# 05_USB_HUB.net
KiCad netlist of a schematic drawn in Altium Designer
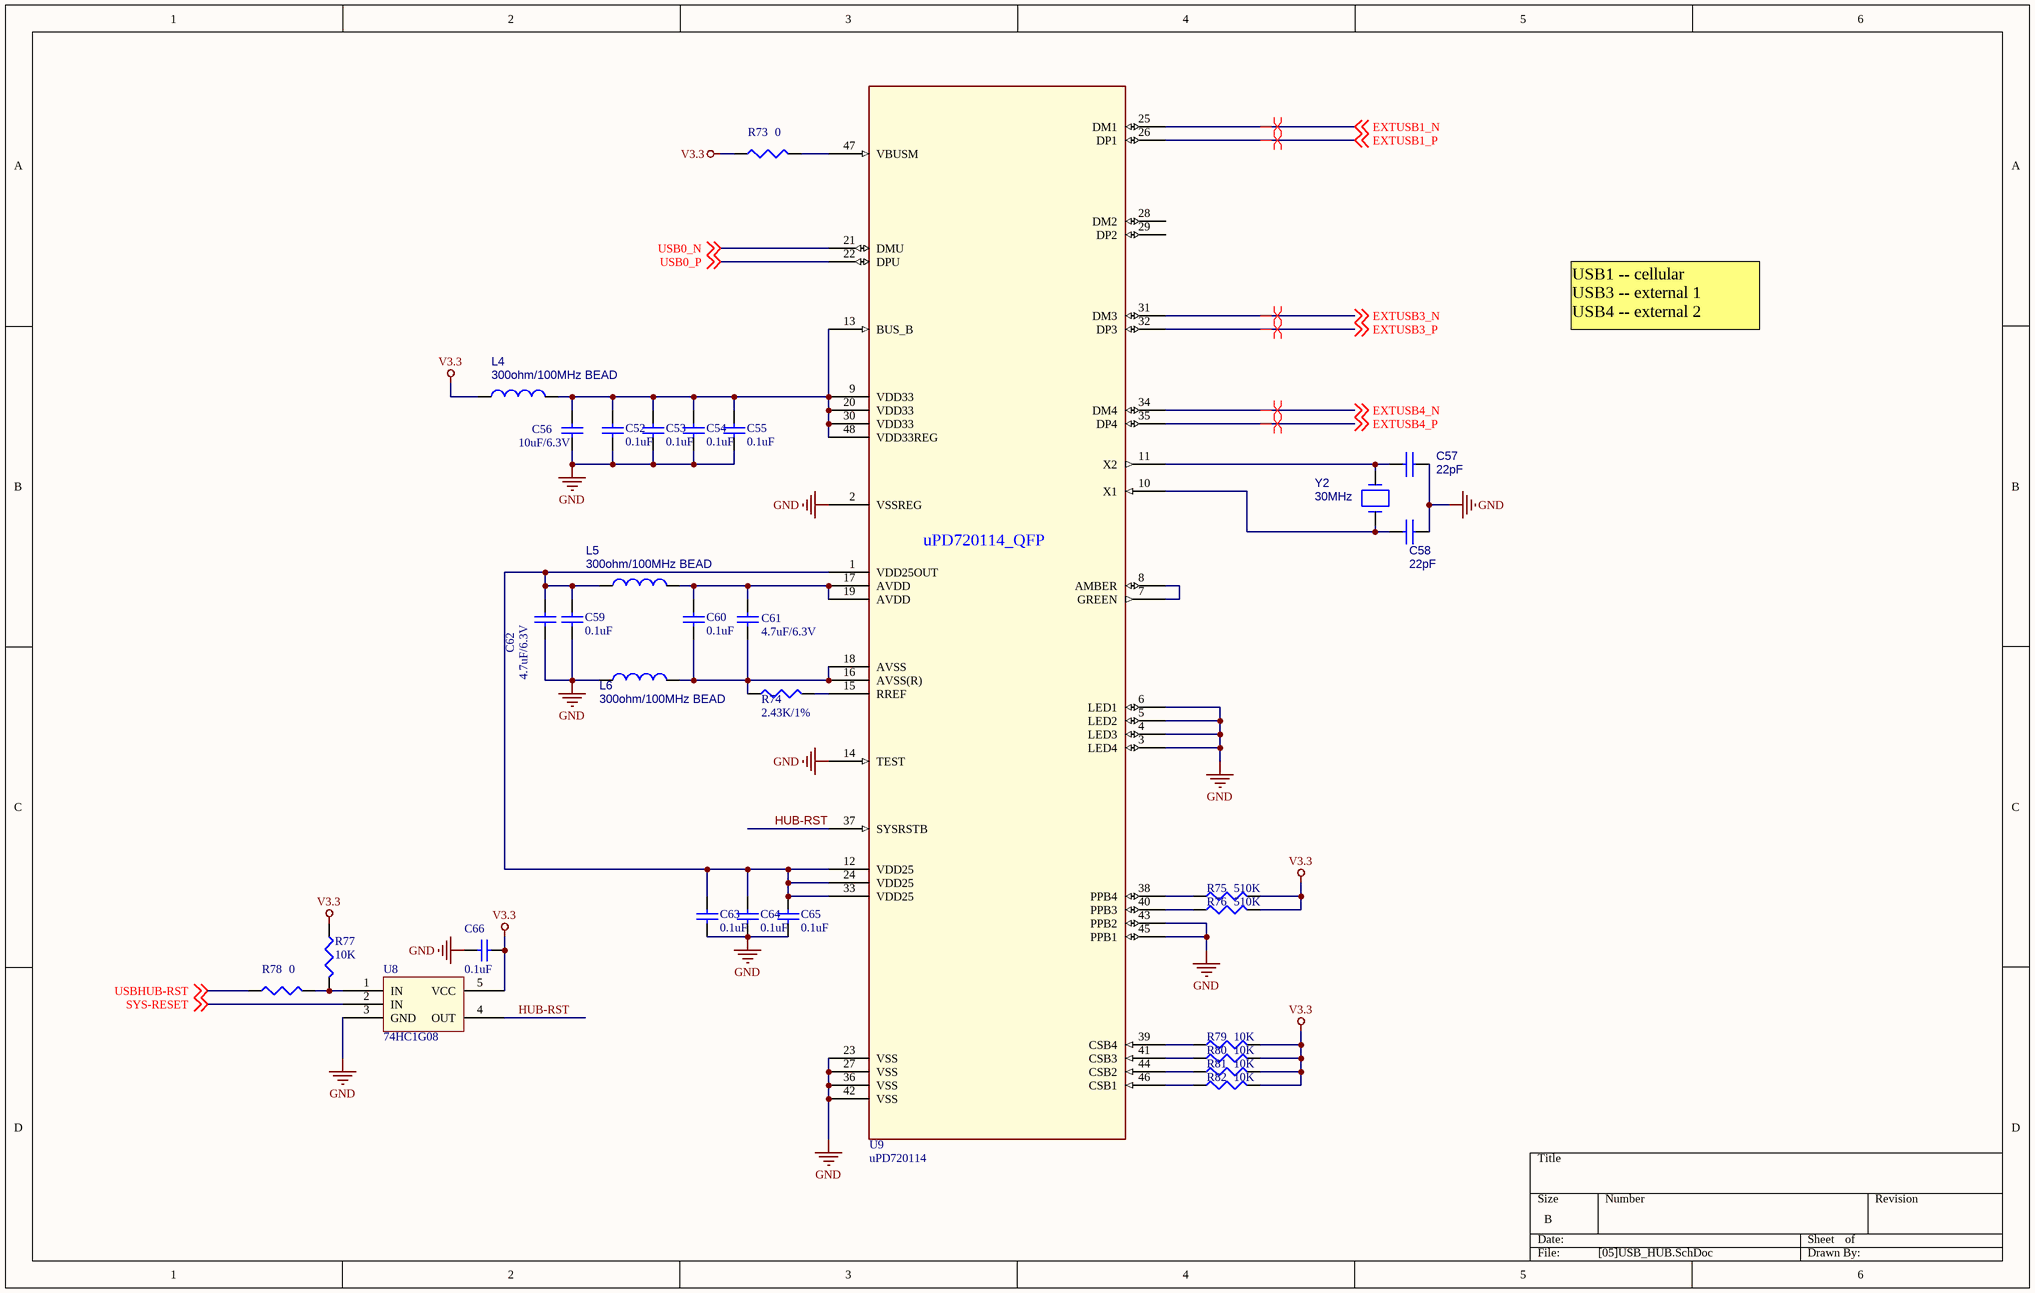
[diagram p0: [05]USB_HUB.SchDoc]

(export (version "E")
  (design (tool "Eeschema 10.0.6"))
  (components
    (comp (ref "C52")
      (value "0.1uF")
      (footprint "0603")
      (description "Capacitor")
      (libsource (lib "Miscellaneous Devices") (part "Cap"))
    )
    (comp (ref "C53")
      (value "0.1uF")
      (footprint "0603")
      (description "Capacitor")
      (libsource (lib "Miscellaneous Devices") (part "Cap"))
    )
    (comp (ref "C54")
      (value "0.1uF")
      (footprint "0603")
      (description "Capacitor")
      (libsource (lib "Miscellaneous Devices") (part "Cap"))
    )
    (comp (ref "C55")
      (value "0.1uF")
      (footprint "0603")
      (description "Capacitor")
      (libsource (lib "Miscellaneous Devices") (part "Cap"))
    )
    (comp (ref "C56")
      (value "10uF/6.3V")
      (footprint "0805")
      (description "Capacitor")
      (libsource (lib "Miscellaneous Devices") (part "Cap"))
    )
    (comp (ref "C57") (value "22pF") (libsource (lib "*") (part "CAP_Dup1")))
    (comp (ref "C58") (value "22pF") (libsource (lib "*") (part "CAP_Dup1")))
    (comp (ref "C59")
      (value "0.1uF")
      (footprint "0603")
      (description "Capacitor")
      (libsource (lib "Miscellaneous Devices") (part "Cap"))
    )
    (comp (ref "C60")
      (value "0.1uF")
      (footprint "0603")
      (description "Capacitor")
      (libsource (lib "Miscellaneous Devices") (part "Cap"))
    )
    (comp (ref "C61")
      (value "4.7uF/6.3V")
      (footprint "0603")
      (description "Capacitor")
      (libsource (lib "Miscellaneous Devices") (part "Cap"))
    )
    (comp (ref "C62")
      (value "4.7uF/6.3V")
      (footprint "0603")
      (description "Capacitor")
      (libsource (lib "Miscellaneous Devices") (part "Cap"))
    )
    (comp (ref "C63")
      (value "0.1uF")
      (footprint "0603")
      (description "Capacitor")
      (libsource (lib "Miscellaneous Devices") (part "Cap"))
    )
    (comp (ref "C64")
      (value "0.1uF")
      (footprint "0603")
      (description "Capacitor")
      (libsource (lib "Miscellaneous Devices") (part "Cap"))
    )
    (comp (ref "C65")
      (value "0.1uF")
      (footprint "0603")
      (description "Capacitor")
      (libsource (lib "Miscellaneous Devices") (part "Cap"))
    )
    (comp (ref "C66")
      (value "0.1uF")
      (footprint "0603")
      (description "Capacitor")
      (libsource (lib "Miscellaneous Devices") (part "Cap"))
    )
    (comp (ref "L4") (value "300ohm/100MHz BEAD") (libsource (lib "*") (part "INDUCTOR_4")))
    (comp (ref "L5") (value "300ohm/100MHz BEAD") (libsource (lib "*") (part "INDUCTOR_4")))
    (comp (ref "L6") (value "300ohm/100MHz BEAD") (libsource (lib "*") (part "INDUCTOR_4")))
    (comp (ref "R73")
      (value "0")
      (footprint "0603")
      (description "Resistor")
      (libsource (lib "Miscellaneous Devices") (part "Res3"))
    )
    (comp (ref "R74")
      (value "2.43K/1%")
      (footprint "0603")
      (description "Resistor")
      (libsource (lib "Miscellaneous Devices") (part "Res3"))
    )
    (comp (ref "R75")
      (value "510K")
      (footprint "0603")
      (description "Resistor")
      (libsource (lib "Miscellaneous Devices") (part "Res3"))
    )
    (comp (ref "R76")
      (value "510K")
      (footprint "0603")
      (description "Resistor")
      (libsource (lib "Miscellaneous Devices") (part "Res3"))
    )
    (comp (ref "R77")
      (value "10K")
      (footprint "0603")
      (description "Resistor")
      (libsource (lib "Miscellaneous Devices") (part "Res3"))
    )
    (comp (ref "R78")
      (value "0")
      (footprint "0603")
      (description "Resistor")
      (libsource (lib "Miscellaneous Devices") (part "Res3"))
    )
    (comp (ref "R79")
      (value "10K")
      (footprint "0603")
      (description "Resistor")
      (libsource (lib "Miscellaneous Devices") (part "Res3"))
    )
    (comp (ref "R80")
      (value "10K")
      (footprint "0603")
      (description "Resistor")
      (libsource (lib "Miscellaneous Devices") (part "Res3"))
    )
    (comp (ref "R81")
      (value "10K")
      (footprint "0603")
      (description "Resistor")
      (libsource (lib "Miscellaneous Devices") (part "Res3"))
    )
    (comp (ref "R82")
      (value "10K")
      (footprint "0603")
      (description "Resistor")
      (libsource (lib "Miscellaneous Devices") (part "Res3"))
    )
    (comp (ref "U8") (value "74HC1G08") (footprint "SOT23-5") (libsource (lib "Schlib") (part "74HC1G08")))
    (comp (ref "U9") (value "uPD720114") (footprint "LQFP48") (libsource (lib "*") (part "upd720114_QFP_4")))
    (comp (ref "Y2") (value "30MHz") (libsource (lib "*") (part "CRYSTAL")))
  )
  (nets
    (net (code "1") (name "/HUB-RST") (class "Default")
      (node (ref "U8") (pin "4") (pinfunction "OUT_4") (pintype "passive"))
      (node (ref "U9") (pin "37") (pinfunction "SYSRSTB_37") (pintype "input"))
    )
    (net (code "2") (name "EXTUSB1_N") (class "Default")
      (node (ref "U9") (pin "25") (pinfunction "DM1_25") (pintype "bidirectional"))
    )
    (net (code "3") (name "EXTUSB1_P") (class "Default")
      (node (ref "U9") (pin "26") (pinfunction "DP1_26") (pintype "bidirectional"))
    )
    (net (code "4") (name "EXTUSB3_N") (class "Default")
      (node (ref "U9") (pin "31") (pinfunction "DM3_31") (pintype "bidirectional"))
    )
    (net (code "5") (name "EXTUSB3_P") (class "Default")
      (node (ref "U9") (pin "32") (pinfunction "DP3_32") (pintype "bidirectional"))
    )
    (net (code "6") (name "EXTUSB4_N") (class "Default")
      (node (ref "U9") (pin "34") (pinfunction "DM4_34") (pintype "bidirectional"))
    )
    (net (code "7") (name "EXTUSB4_P") (class "Default")
      (node (ref "U9") (pin "35") (pinfunction "DP4_35") (pintype "bidirectional"))
    )
    (net (code "8") (name "GND") (class "Default")
      (node (ref "C52") (pin "1") (pinfunction "1_1") (pintype "passive"))
      (node (ref "C53") (pin "1") (pinfunction "1_1") (pintype "passive"))
      (node (ref "C54") (pin "1") (pinfunction "1_1") (pintype "passive"))
      (node (ref "C55") (pin "1") (pinfunction "1_1") (pintype "passive"))
      (node (ref "C56") (pin "1") (pinfunction "1_1") (pintype "passive"))
      (node (ref "C57") (pin "1") (pinfunction "1_1") (pintype "passive"))
      (node (ref "C58") (pin "1") (pinfunction "1_1") (pintype "passive"))
      (node (ref "C59") (pin "1") (pinfunction "1_1") (pintype "passive"))
      (node (ref "C62") (pin "1") (pinfunction "1_1") (pintype "passive"))
      (node (ref "C63") (pin "1") (pinfunction "1_1") (pintype "passive"))
      (node (ref "C64") (pin "1") (pinfunction "1_1") (pintype "passive"))
      (node (ref "C65") (pin "1") (pinfunction "1_1") (pintype "passive"))
      (node (ref "C66") (pin "2") (pinfunction "2_2") (pintype "passive"))
      (node (ref "L6") (pin "2") (pinfunction "2_2") (pintype "passive"))
      (node (ref "U8") (pin "3") (pinfunction "GND_3") (pintype "passive"))
      (node (ref "U9") (pin "14") (pinfunction "TEST_14") (pintype "input"))
      (node (ref "U9") (pin "2") (pinfunction "VSSREG_2") (pintype "power_in"))
      (node (ref "U9") (pin "23") (pinfunction "VSS_23") (pintype "power_in"))
      (node (ref "U9") (pin "27") (pinfunction "VSS_27") (pintype "power_in"))
      (node (ref "U9") (pin "3") (pinfunction "LED4_3") (pintype "bidirectional"))
      (node (ref "U9") (pin "36") (pinfunction "VSS_36") (pintype "power_in"))
      (node (ref "U9") (pin "4") (pinfunction "LED3_4") (pintype "bidirectional"))
      (node (ref "U9") (pin "42") (pinfunction "VSS_42") (pintype "power_in"))
      (node (ref "U9") (pin "43") (pinfunction "PPB2_43") (pintype "bidirectional"))
      (node (ref "U9") (pin "45") (pinfunction "PPB1_45") (pintype "bidirectional"))
      (node (ref "U9") (pin "5") (pinfunction "LED2_5") (pintype "bidirectional"))
      (node (ref "U9") (pin "6") (pinfunction "LED1_6") (pintype "bidirectional"))
    )
    (net (code "9") (name "Net-(C60-Pad2)") (class "Default")
      (node (ref "C60") (pin "2") (pinfunction "2_2") (pintype "passive"))
      (node (ref "C61") (pin "2") (pinfunction "2_2") (pintype "passive"))
      (node (ref "L5") (pin "1") (pinfunction "1_1") (pintype "passive"))
      (node (ref "U9") (pin "17") (pinfunction "AVDD_17") (pintype "power_in"))
      (node (ref "U9") (pin "19") (pinfunction "AVDD_19") (pintype "power_in"))
    )
    (net (code "10") (name "Net-(R77-Pad2)") (class "Default")
      (node (ref "R77") (pin "2") (pinfunction "2_2") (pintype "passive"))
      (node (ref "R78") (pin "2") (pinfunction "2_2") (pintype "passive"))
      (node (ref "U8") (pin "1") (pinfunction "IN_1") (pintype "passive"))
    )
    (net (code "11") (name "Net-(U9-AMBER)") (class "Default")
      (node (ref "U9") (pin "7") (pinfunction "GREEN_7") (pintype "output"))
      (node (ref "U9") (pin "8") (pinfunction "AMBER_8") (pintype "bidirectional"))
    )
    (net (code "12") (name "Net-(U9-AVSS(R))") (class "Default")
      (node (ref "C60") (pin "1") (pinfunction "1_1") (pintype "passive"))
      (node (ref "C61") (pin "1") (pinfunction "1_1") (pintype "passive"))
      (node (ref "L6") (pin "1") (pinfunction "1_1") (pintype "passive"))
      (node (ref "R74") (pin "1") (pinfunction "1_1") (pintype "passive"))
      (node (ref "U9") (pin "16") (pinfunction "AVSS(R)_16") (pintype "power_in"))
      (node (ref "U9") (pin "18") (pinfunction "AVSS_18") (pintype "power_in"))
    )
    (net (code "13") (name "Net-(U9-BUS_B)") (class "Default")
      (node (ref "C52") (pin "2") (pinfunction "2_2") (pintype "passive"))
      (node (ref "C53") (pin "2") (pinfunction "2_2") (pintype "passive"))
      (node (ref "C54") (pin "2") (pinfunction "2_2") (pintype "passive"))
      (node (ref "C55") (pin "2") (pinfunction "2_2") (pintype "passive"))
      (node (ref "C56") (pin "2") (pinfunction "2_2") (pintype "passive"))
      (node (ref "L4") (pin "1") (pinfunction "1_1") (pintype "passive"))
      (node (ref "U9") (pin "13") (pinfunction "BUS_B_13") (pintype "input"))
      (node (ref "U9") (pin "20") (pinfunction "VDD33_20") (pintype "power_in"))
      (node (ref "U9") (pin "30") (pinfunction "VDD33_30") (pintype "power_in"))
      (node (ref "U9") (pin "48") (pinfunction "VDD33REG_48") (pintype "power_in"))
      (node (ref "U9") (pin "9") (pinfunction "VDD33_9") (pintype "power_in"))
    )
    (net (code "14") (name "Net-(U9-CSB1)") (class "Default")
      (node (ref "R82") (pin "1") (pinfunction "1_1") (pintype "passive"))
      (node (ref "U9") (pin "46") (pinfunction "CSB1_46") (pintype "input"))
    )
    (net (code "15") (name "Net-(U9-CSB2)") (class "Default")
      (node (ref "R81") (pin "1") (pinfunction "1_1") (pintype "passive"))
      (node (ref "U9") (pin "44") (pinfunction "CSB2_44") (pintype "input"))
    )
    (net (code "16") (name "Net-(U9-CSB3)") (class "Default")
      (node (ref "R80") (pin "1") (pinfunction "1_1") (pintype "passive"))
      (node (ref "U9") (pin "41") (pinfunction "CSB3_41") (pintype "input"))
    )
    (net (code "17") (name "Net-(U9-CSB4)") (class "Default")
      (node (ref "R79") (pin "1") (pinfunction "1_1") (pintype "passive"))
      (node (ref "U9") (pin "39") (pinfunction "CSB4_39") (pintype "input"))
    )
    (net (code "18") (name "Net-(U9-PPB3)") (class "Default")
      (node (ref "R76") (pin "1") (pinfunction "1_1") (pintype "passive"))
      (node (ref "U9") (pin "40") (pinfunction "PPB3_40") (pintype "bidirectional"))
    )
    (net (code "19") (name "Net-(U9-PPB4)") (class "Default")
      (node (ref "R75") (pin "1") (pinfunction "1_1") (pintype "passive"))
      (node (ref "U9") (pin "38") (pinfunction "PPB4_38") (pintype "bidirectional"))
    )
    (net (code "20") (name "Net-(U9-RREF)") (class "Default")
      (node (ref "R74") (pin "2") (pinfunction "2_2") (pintype "passive"))
      (node (ref "U9") (pin "15") (pinfunction "RREF_15") (pintype "passive"))
    )
    (net (code "21") (name "Net-(U9-VBUSM)") (class "Default")
      (node (ref "R73") (pin "2") (pinfunction "2_2") (pintype "passive"))
      (node (ref "U9") (pin "47") (pinfunction "VBUSM_47") (pintype "input"))
    )
    (net (code "22") (name "Net-(U9-VDD25OUT)") (class "Default")
      (node (ref "C59") (pin "2") (pinfunction "2_2") (pintype "passive"))
      (node (ref "C62") (pin "2") (pinfunction "2_2") (pintype "passive"))
      (node (ref "C63") (pin "2") (pinfunction "2_2") (pintype "passive"))
      (node (ref "C64") (pin "2") (pinfunction "2_2") (pintype "passive"))
      (node (ref "C65") (pin "2") (pinfunction "2_2") (pintype "passive"))
      (node (ref "L5") (pin "2") (pinfunction "2_2") (pintype "passive"))
      (node (ref "U9") (pin "1") (pinfunction "VDD25OUT_1") (pintype "power_in"))
      (node (ref "U9") (pin "12") (pinfunction "VDD25_12") (pintype "power_in"))
      (node (ref "U9") (pin "24") (pinfunction "VDD25_24") (pintype "power_in"))
      (node (ref "U9") (pin "33") (pinfunction "VDD25_33") (pintype "power_in"))
    )
    (net (code "23") (name "Net-(U9-X1)") (class "Default")
      (node (ref "C58") (pin "2") (pinfunction "2_2") (pintype "passive"))
      (node (ref "U9") (pin "10") (pinfunction "X1_10") (pintype "input"))
      (node (ref "Y2") (pin "1") (pinfunction "1_1") (pintype "passive"))
    )
    (net (code "24") (name "Net-(U9-X2)") (class "Default")
      (node (ref "C57") (pin "2") (pinfunction "2_2") (pintype "passive"))
      (node (ref "U9") (pin "11") (pinfunction "X2_11") (pintype "output"))
      (node (ref "Y2") (pin "2") (pinfunction "2_2") (pintype "passive"))
    )
    (net (code "25") (name "SYS-RESET") (class "Default")
      (node (ref "U8") (pin "2") (pinfunction "IN_2") (pintype "passive"))
    )
    (net (code "26") (name "USB0_N") (class "Default")
      (node (ref "U9") (pin "21") (pinfunction "DMU_21") (pintype "bidirectional"))
    )
    (net (code "27") (name "USB0_P") (class "Default")
      (node (ref "U9") (pin "22") (pinfunction "DPU_22") (pintype "bidirectional"))
    )
    (net (code "28") (name "USBHUB-RST") (class "Default")
      (node (ref "R78") (pin "1") (pinfunction "1_1") (pintype "passive"))
    )
    (net (code "29") (name "V3.3") (class "Default")
      (node (ref "C66") (pin "1") (pinfunction "1_1") (pintype "passive"))
      (node (ref "L4") (pin "2") (pinfunction "2_2") (pintype "passive"))
      (node (ref "R73") (pin "1") (pinfunction "1_1") (pintype "passive"))
      (node (ref "R75") (pin "2") (pinfunction "2_2") (pintype "passive"))
      (node (ref "R76") (pin "2") (pinfunction "2_2") (pintype "passive"))
      (node (ref "R77") (pin "1") (pinfunction "1_1") (pintype "passive"))
      (node (ref "R79") (pin "2") (pinfunction "2_2") (pintype "passive"))
      (node (ref "R80") (pin "2") (pinfunction "2_2") (pintype "passive"))
      (node (ref "R81") (pin "2") (pinfunction "2_2") (pintype "passive"))
      (node (ref "R82") (pin "2") (pinfunction "2_2") (pintype "passive"))
      (node (ref "U8") (pin "5") (pinfunction "VCC_5") (pintype "passive"))
    )
    (net (code "30") (name "unconnected-(U9-DM2-Pad28)") (class "Default")
      (node (ref "U9") (pin "28") (pinfunction "DM2_28") (pintype "bidirectional"))
    )
    (net (code "31") (name "unconnected-(U9-DP2-Pad29)") (class "Default")
      (node (ref "U9") (pin "29") (pinfunction "DP2_29") (pintype "bidirectional"))
    )
  )
)
